# NEURON-Z1_EASYEDA.net
KiCad netlist of a schematic drawn in EasyEDA
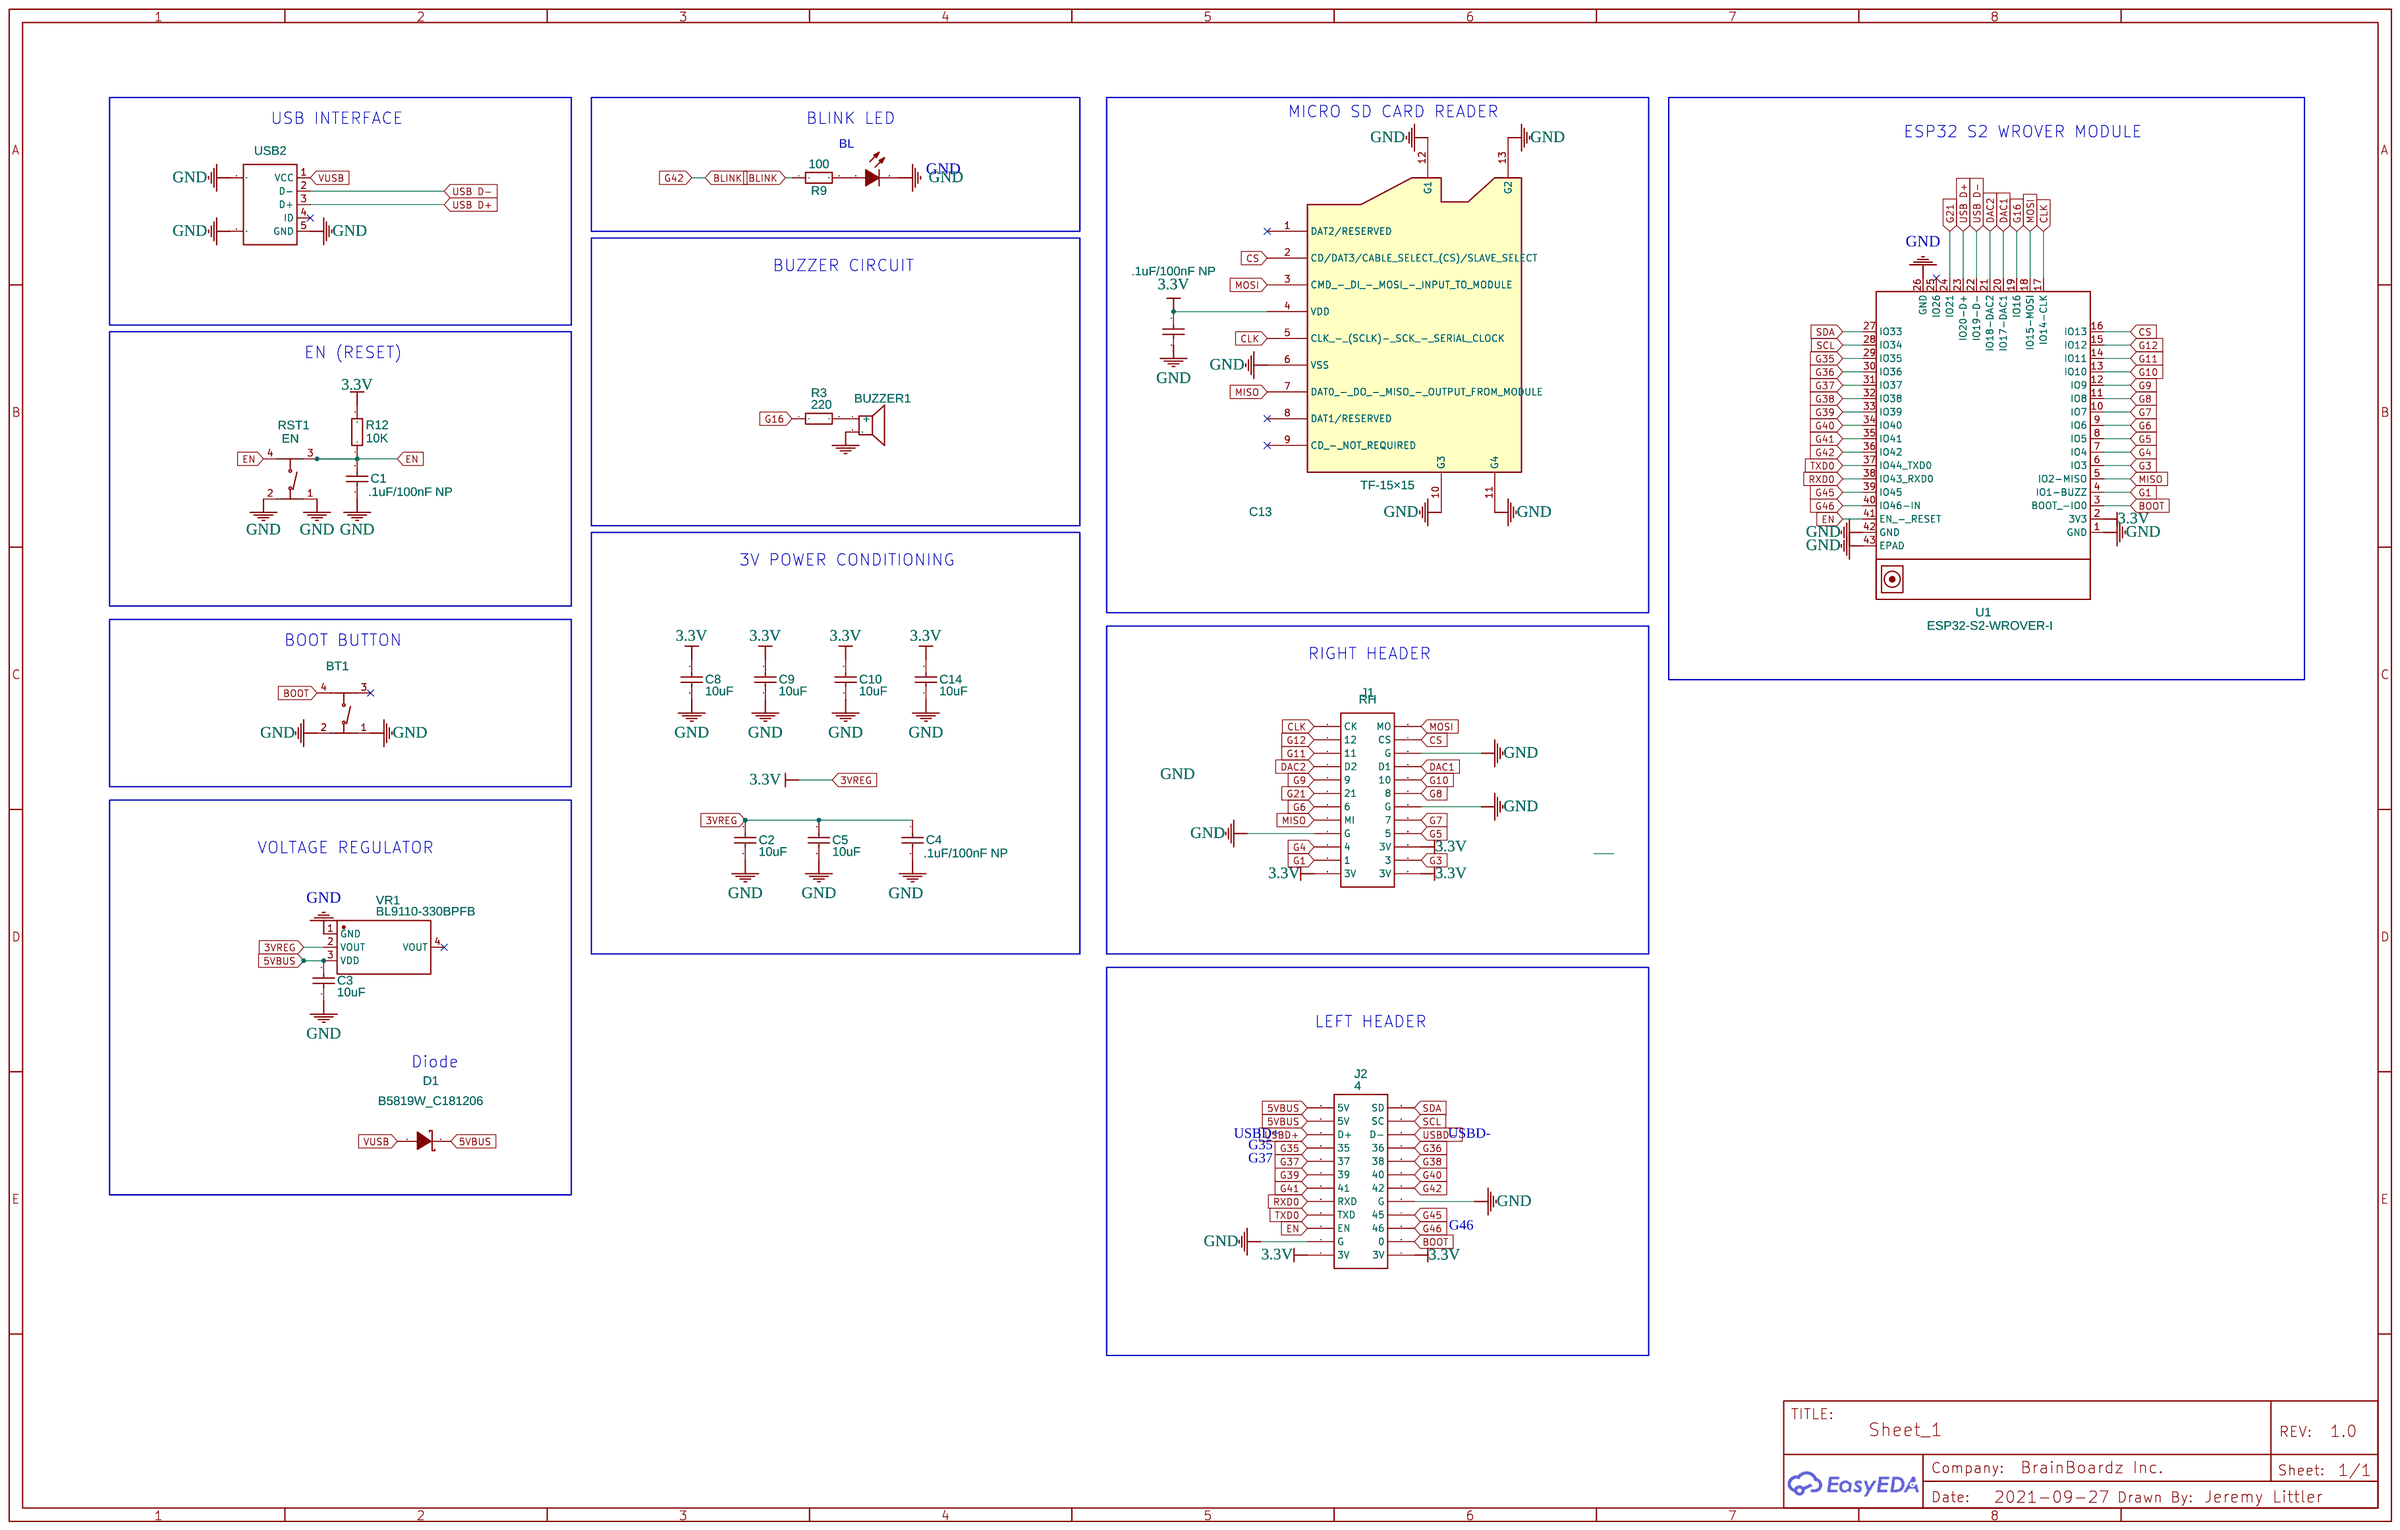
[diagram p0: schematic sheet]

(export (version "E")
  (design (tool "Eeschema 10.0.6"))
  (components
    (comp (ref "BLINK1")
      (value "15-21SYGC/S530-E2/TR8")
      (fields (field (name "BOM_Supplier Part") "C73550"))
      (libsource (lib "") (part "15-21SYGC/S530-E2/TR8"))
    )
    (comp (ref "BT1")
      (value "BOOT")
      (fields
        (field (name "BOM_Manufacturer Part") "TS-1187A-C-E-B")
        (field (name "BOM_Supplier Part") "C318887")
      )
      (libsource (lib "") (part "TS-1187A-C-E-B"))
    )
    (comp (ref "BUZZER1")
      (value "PS1240P02CT3")
      (fields (field (name "BOM_Supplier Part") "C76873"))
      (libsource (lib "") (part "PS1240P02CT3"))
    )
    (comp (ref "C1")
      (value ".1uF/100nF NP")
      (fields
        (field (name "BOM_Manufacturer Part") "CL31B104KBCNNNC")
        (field (name "BOM_Supplier Part") "C24497")
      )
      (libsource (lib "") (part "CL31B104KBCNNNC"))
    )
    (comp (ref "C2")
      (value "10uF")
      (fields
        (field (name "BOM_Manufacturer Part") "CL31A106KBHNNNE")
        (field (name "BOM_Supplier Part") "C13585")
      )
      (libsource (lib "") (part "CL31A106KBHNNNE"))
    )
    (comp (ref "C3")
      (value "10uF")
      (fields
        (field (name "BOM_Manufacturer Part") "CL31A106KBHNNNE")
        (field (name "BOM_Supplier Part") "C13585")
      )
      (libsource (lib "") (part "CL31A106KBHNNNE"))
    )
    (comp (ref "C4")
      (value ".1uF/100nF NP")
      (fields
        (field (name "BOM_Manufacturer Part") "CL31B104KBCNNNC")
        (field (name "BOM_Supplier Part") "C24497")
      )
      (libsource (lib "") (part "CL31B104KBCNNNC"))
    )
    (comp (ref "C5")
      (value "10uF")
      (fields
        (field (name "BOM_Manufacturer Part") "CL31A106KBHNNNE")
        (field (name "BOM_Supplier Part") "C13585")
      )
      (libsource (lib "") (part "CL31A106KBHNNNE"))
    )
    (comp (ref "C8")
      (value "10uF")
      (fields
        (field (name "BOM_Manufacturer Part") "CL31A106KBHNNNE")
        (field (name "BOM_Supplier Part") "C13585")
      )
      (libsource (lib "") (part "CL31A106KBHNNNE"))
    )
    (comp (ref "C9")
      (value "10uF")
      (fields
        (field (name "BOM_Manufacturer Part") "CL31A106KBHNNNE")
        (field (name "BOM_Supplier Part") "C13585")
      )
      (libsource (lib "") (part "CL31A106KBHNNNE"))
    )
    (comp (ref "C10")
      (value "10uF")
      (fields
        (field (name "BOM_Manufacturer Part") "CL31A106KBHNNNE")
        (field (name "BOM_Supplier Part") "C13585")
      )
      (libsource (lib "") (part "CL31A106KBHNNNE"))
    )
    (comp (ref "C13")
      (value ".1uF/100nF NP")
      (fields
        (field (name "BOM_Manufacturer Part") "CL31B104KBCNNNC")
        (field (name "BOM_Supplier Part") "C24497")
      )
      (libsource (lib "") (part "CL31B104KBCNNNC_1"))
    )
    (comp (ref "C14")
      (value "10uF")
      (fields
        (field (name "BOM_Manufacturer Part") "CL31A106KBHNNNE")
        (field (name "BOM_Supplier Part") "C13585")
      )
      (libsource (lib "") (part "CL31A106KBHNNNE"))
    )
    (comp (ref "D1")
      (value "B5819W_C181206")
      (fields (field (name "BOM_Manufacturer Part") "B5819W") (field (name "BOM_Supplier Part") "C181206"))
      (libsource (lib "") (part "B5819W_C181206"))
    )
    (comp (ref "J1")
      (value "RH")
      (fields (field (name "BOM_Manufacturer Part") "New SchematicLib"))
      (libsource (lib "") (part "HDR 2.54mm 2x12_1"))
    )
    (comp (ref "J2")
      (value "4")
      (fields (field (name "BOM_Manufacturer Part") "New SchematicLib"))
      (libsource (lib "") (part "HDR 2.54mm 2x12"))
    )
    (comp (ref "MICROSD1")
      (value "TF-15×15")
      (fields (field (name "BOM_Supplier Part") "C111196"))
      (libsource (lib "") (part "TF-15×15"))
    )
    (comp (ref "R3")
      (value "220")
      (fields
        (field (name "BOM_Manufacturer Part") "1206W4J0221T5E")
        (field (name "BOM_Supplier Part") "C25363")
      )
      (libsource (lib "") (part "1206W4J0221T5E"))
    )
    (comp (ref "R9")
      (value "100")
      (fields
        (field (name "BOM_Manufacturer Part") "1206W4F1000T5E")
        (field (name "BOM_Supplier Part") "C17901")
      )
      (libsource (lib "") (part "1206W4F1000T5E"))
    )
    (comp (ref "R12")
      (value "10K")
      (fields
        (field (name "BOM_Manufacturer Part") "AECR1206F10K0K9")
        (field (name "BOM_Supplier Part") "C328409")
      )
      (libsource (lib "") (part "AECR1206F10K0K9"))
    )
    (comp (ref "RST1")
      (value "EN")
      (fields
        (field (name "BOM_Manufacturer Part") "TS-1187A-C-E-B")
        (field (name "BOM_Supplier Part") "C318887")
      )
      (libsource (lib "") (part "TS-1187A-C-E-B_1"))
    )
    (comp (ref "U1") (value "ESP32-S2-WROVER-I") (libsource (lib "") (part "ESP32-S2-WROVER-I")))
    (comp (ref "USB2")
      (value "Mini USB-B 5P-Female-TH_C46398")
      (fields
        (field (name "BOM_Manufacturer Part") "MINI 5PFemale90Degree plate four feet copper shell LCPVinyl")
        (field (name "BOM_Supplier Part") "C46398")
      )
      (libsource (lib "") (part "Mini USB-B 5P-Female-TH_C46398"))
    )
    (comp (ref "VR1")
      (value "BL9110-330BPFB")
      (fields (field (name "BOM_Supplier Part") "C169246"))
      (libsource (lib "") (part "BL9110-330BPFB"))
    )
  )
  (nets
    (net (code "1") (name "3VREG") (class "Default")
      (node (ref "C10") (pin "2") (pinfunction "2_2") (pintype "input"))
      (node (ref "C13") (pin "2") (pinfunction "2_2") (pintype "input"))
      (node (ref "C14") (pin "2") (pinfunction "2_2") (pintype "input"))
      (node (ref "C2") (pin "2") (pinfunction "2_2") (pintype "input"))
      (node (ref "C4") (pin "1") (pinfunction "1_1") (pintype "input"))
      (node (ref "C5") (pin "2") (pinfunction "2_2") (pintype "input"))
      (node (ref "C8") (pin "2") (pinfunction "2_2") (pintype "input"))
      (node (ref "C9") (pin "2") (pinfunction "2_2") (pintype "input"))
      (node (ref "J1") (pin "20") (pinfunction "3V_20") (pintype "unspecified"))
      (node (ref "J1") (pin "23") (pinfunction "3V_23") (pintype "unspecified"))
      (node (ref "J1") (pin "24") (pinfunction "3V_24") (pintype "unspecified"))
      (node (ref "J2") (pin "1") (pinfunction "3V_1") (pintype "unspecified"))
      (node (ref "J2") (pin "2") (pinfunction "3V_2") (pintype "unspecified"))
      (node (ref "MICROSD1") (pin "4") (pinfunction "VDD_4") (pintype "input"))
      (node (ref "R12") (pin "2") (pinfunction "2_2") (pintype "unspecified"))
      (node (ref "U1") (pin "2") (pinfunction "3V3_2") (pintype "unspecified"))
      (node (ref "VR1") (pin "2") (pinfunction "VOUT_2") (pintype "unspecified"))
    )
    (net (code "2") (name "5VBUS") (class "Default")
      (node (ref "C3") (pin "2") (pinfunction "2_2") (pintype "input"))
      (node (ref "D1") (pin "1") (pinfunction "K_1") (pintype "unspecified"))
      (node (ref "J2") (pin "22") (pinfunction "5V_22") (pintype "unspecified"))
      (node (ref "J2") (pin "24") (pinfunction "5V_24") (pintype "unspecified"))
      (node (ref "VR1") (pin "3") (pinfunction "VDD_3") (pintype "unspecified"))
    )
    (net (code "3") (name "BLINK") (class "Default")
      (node (ref "J2") (pin "11") (pinfunction "42_11") (pintype "unspecified"))
      (node (ref "R9") (pin "1") (pinfunction "1_1") (pintype "input"))
      (node (ref "U1") (pin "36") (pinfunction "IO42_36") (pintype "unspecified"))
    )
    (net (code "4") (name "BOOT") (class "Default")
      (node (ref "BT1") (pin "4") (pinfunction "D_4") (pintype "unspecified"))
      (node (ref "J2") (pin "3") (pinfunction "0_3") (pintype "unspecified"))
      (node (ref "U1") (pin "3") (pinfunction "BOOT_-IO0_3") (pintype "unspecified"))
    )
    (net (code "5") (name "CLK") (class "Default")
      (node (ref "J1") (pin "1") (pinfunction "CK_1") (pintype "unspecified"))
      (node (ref "MICROSD1") (pin "5") (pinfunction "CLK_-_(SCLK)-_SCK_-_SERIAL_CLOCK_5") (pintype "input"))
      (node (ref "U1") (pin "17") (pinfunction "IO14-CLK_17") (pintype "unspecified"))
    )
    (net (code "6") (name "CS") (class "Default")
      (node (ref "J1") (pin "4") (pinfunction "CS_4") (pintype "unspecified"))
      (node (ref "MICROSD1") (pin "2") (pinfunction "CD/DAT3/CABLE_SELECT_(CS)/SLAVE_SELECT_2") (pintype "input"))
      (node (ref "U1") (pin "16") (pinfunction "IO13_16") (pintype "unspecified"))
    )
    (net (code "7") (name "DAC1") (class "Default")
      (node (ref "J1") (pin "8") (pinfunction "D1_8") (pintype "unspecified"))
      (node (ref "U1") (pin "20") (pinfunction "IO17-DAC1_20") (pintype "unspecified"))
    )
    (net (code "8") (name "DAC2") (class "Default")
      (node (ref "J1") (pin "7") (pinfunction "D2_7") (pintype "unspecified"))
      (node (ref "U1") (pin "21") (pinfunction "IO18-DAC2_21") (pintype "unspecified"))
    )
    (net (code "9") (name "EN") (class "Default")
      (node (ref "C1") (pin "1") (pinfunction "1_1") (pintype "input"))
      (node (ref "J2") (pin "6") (pinfunction "EN_6") (pintype "unspecified"))
      (node (ref "R12") (pin "1") (pinfunction "1_1") (pintype "unspecified"))
      (node (ref "RST1") (pin "3") (pinfunction "C_3") (pintype "unspecified"))
      (node (ref "RST1") (pin "4") (pinfunction "D_4") (pintype "unspecified"))
      (node (ref "U1") (pin "41") (pinfunction "EN_-_RESET_41") (pintype "unspecified"))
    )
    (net (code "10") (name "G1") (class "Default")
      (node (ref "J1") (pin "21") (pinfunction "1_21") (pintype "unspecified"))
      (node (ref "U1") (pin "4") (pinfunction "IO1-BUZZ_4") (pintype "unspecified"))
    )
    (net (code "11") (name "G3") (class "Default")
      (node (ref "J1") (pin "22") (pinfunction "3_22") (pintype "unspecified"))
      (node (ref "U1") (pin "6") (pinfunction "IO3_6") (pintype "unspecified"))
    )
    (net (code "12") (name "G4") (class "Default")
      (node (ref "J1") (pin "19") (pinfunction "4_19") (pintype "unspecified"))
      (node (ref "U1") (pin "7") (pinfunction "IO4_7") (pintype "unspecified"))
    )
    (net (code "13") (name "G5") (class "Default")
      (node (ref "J1") (pin "18") (pinfunction "5_18") (pintype "unspecified"))
      (node (ref "U1") (pin "8") (pinfunction "IO5_8") (pintype "unspecified"))
    )
    (net (code "14") (name "G6") (class "Default")
      (node (ref "J1") (pin "13") (pinfunction "6_13") (pintype "unspecified"))
      (node (ref "U1") (pin "9") (pinfunction "IO6_9") (pintype "unspecified"))
    )
    (net (code "15") (name "G7") (class "Default")
      (node (ref "J1") (pin "16") (pinfunction "7_16") (pintype "unspecified"))
      (node (ref "U1") (pin "10") (pinfunction "IO7_10") (pintype "unspecified"))
    )
    (net (code "16") (name "G8") (class "Default")
      (node (ref "J1") (pin "12") (pinfunction "8_12") (pintype "unspecified"))
      (node (ref "U1") (pin "11") (pinfunction "IO8_11") (pintype "unspecified"))
    )
    (net (code "17") (name "G9") (class "Default")
      (node (ref "J1") (pin "9") (pinfunction "9_9") (pintype "unspecified"))
      (node (ref "U1") (pin "12") (pinfunction "IO9_12") (pintype "unspecified"))
    )
    (net (code "18") (name "G10") (class "Default")
      (node (ref "J1") (pin "10") (pinfunction "10_10") (pintype "unspecified"))
      (node (ref "U1") (pin "13") (pinfunction "IO10_13") (pintype "unspecified"))
    )
    (net (code "19") (name "G11") (class "Default")
      (node (ref "J1") (pin "5") (pinfunction "11_5") (pintype "unspecified"))
      (node (ref "U1") (pin "14") (pinfunction "IO11_14") (pintype "unspecified"))
    )
    (net (code "20") (name "G12") (class "Default")
      (node (ref "J1") (pin "3") (pinfunction "12_3") (pintype "unspecified"))
      (node (ref "U1") (pin "15") (pinfunction "IO12_15") (pintype "unspecified"))
    )
    (net (code "21") (name "G16") (class "Default")
      (node (ref "R3") (pin "1") (pinfunction "1_1") (pintype "input"))
      (node (ref "U1") (pin "19") (pinfunction "IO16_19") (pintype "unspecified"))
    )
    (net (code "22") (name "G21") (class "Default")
      (node (ref "J1") (pin "11") (pinfunction "21_11") (pintype "unspecified"))
      (node (ref "U1") (pin "24") (pinfunction "IO21_24") (pintype "unspecified"))
    )
    (net (code "23") (name "G35") (class "Default")
      (node (ref "J2") (pin "18") (pinfunction "35_18") (pintype "unspecified"))
      (node (ref "U1") (pin "29") (pinfunction "IO35_29") (pintype "unspecified"))
    )
    (net (code "24") (name "G36") (class "Default")
      (node (ref "J2") (pin "17") (pinfunction "36_17") (pintype "unspecified"))
      (node (ref "U1") (pin "30") (pinfunction "IO36_30") (pintype "unspecified"))
    )
    (net (code "25") (name "G37") (class "Default")
      (node (ref "J2") (pin "16") (pinfunction "37_16") (pintype "unspecified"))
      (node (ref "U1") (pin "31") (pinfunction "IO37_31") (pintype "unspecified"))
    )
    (net (code "26") (name "G38") (class "Default")
      (node (ref "J2") (pin "15") (pinfunction "38_15") (pintype "unspecified"))
      (node (ref "U1") (pin "32") (pinfunction "IO38_32") (pintype "unspecified"))
    )
    (net (code "27") (name "G39") (class "Default")
      (node (ref "J2") (pin "14") (pinfunction "39_14") (pintype "unspecified"))
      (node (ref "U1") (pin "33") (pinfunction "IO39_33") (pintype "unspecified"))
    )
    (net (code "28") (name "G40") (class "Default")
      (node (ref "J2") (pin "13") (pinfunction "40_13") (pintype "unspecified"))
      (node (ref "U1") (pin "34") (pinfunction "IO40_34") (pintype "unspecified"))
    )
    (net (code "29") (name "G41") (class "Default")
      (node (ref "J2") (pin "12") (pinfunction "41_12") (pintype "unspecified"))
      (node (ref "U1") (pin "35") (pinfunction "IO41_35") (pintype "unspecified"))
    )
    (net (code "30") (name "G45") (class "Default")
      (node (ref "J2") (pin "7") (pinfunction "45_7") (pintype "unspecified"))
      (node (ref "U1") (pin "39") (pinfunction "IO45_39") (pintype "unspecified"))
    )
    (net (code "31") (name "G46") (class "Default")
      (node (ref "J2") (pin "5") (pinfunction "46_5") (pintype "unspecified"))
      (node (ref "U1") (pin "40") (pinfunction "IO46-IN_40") (pintype "unspecified"))
    )
    (net (code "32") (name "GND") (class "Default")
      (node (ref "BLINK1") (pin "2") (pinfunction "C_2") (pintype "input"))
      (node (ref "BT1") (pin "1") (pinfunction "A_1") (pintype "unspecified"))
      (node (ref "BT1") (pin "2") (pinfunction "B_2") (pintype "unspecified"))
      (node (ref "BUZZER1") (pin "2") (pinfunction "2_2") (pintype "unspecified"))
      (node (ref "C1") (pin "2") (pinfunction "2_2") (pintype "input"))
      (node (ref "C10") (pin "1") (pinfunction "1_1") (pintype "input"))
      (node (ref "C13") (pin "1") (pinfunction "1_1") (pintype "input"))
      (node (ref "C14") (pin "1") (pinfunction "1_1") (pintype "input"))
      (node (ref "C2") (pin "1") (pinfunction "1_1") (pintype "input"))
      (node (ref "C3") (pin "1") (pinfunction "1_1") (pintype "input"))
      (node (ref "C4") (pin "2") (pinfunction "2_2") (pintype "input"))
      (node (ref "C5") (pin "1") (pinfunction "1_1") (pintype "input"))
      (node (ref "C8") (pin "1") (pinfunction "1_1") (pintype "input"))
      (node (ref "C9") (pin "1") (pinfunction "1_1") (pintype "input"))
      (node (ref "J1") (pin "14") (pinfunction "G_14") (pintype "unspecified"))
      (node (ref "J1") (pin "17") (pinfunction "G_17") (pintype "unspecified"))
      (node (ref "J1") (pin "6") (pinfunction "G_6") (pintype "unspecified"))
      (node (ref "J2") (pin "4") (pinfunction "G_4") (pintype "unspecified"))
      (node (ref "J2") (pin "9") (pinfunction "G_9") (pintype "unspecified"))
      (node (ref "MICROSD1") (pin "10") (pinfunction "G3_10") (pintype "input"))
      (node (ref "MICROSD1") (pin "11") (pinfunction "G4_11") (pintype "input"))
      (node (ref "MICROSD1") (pin "12") (pinfunction "G1_12") (pintype "input"))
      (node (ref "MICROSD1") (pin "13") (pinfunction "G2_13") (pintype "input"))
      (node (ref "MICROSD1") (pin "6") (pinfunction "VSS_6") (pintype "input"))
      (node (ref "RST1") (pin "1") (pinfunction "A_1") (pintype "unspecified"))
      (node (ref "RST1") (pin "2") (pinfunction "B_2") (pintype "unspecified"))
      (node (ref "U1") (pin "1") (pinfunction "GND_1") (pintype "unspecified"))
      (node (ref "U1") (pin "26") (pinfunction "GND_26") (pintype "unspecified"))
      (node (ref "U1") (pin "42") (pinfunction "GND_42") (pintype "unspecified"))
      (node (ref "U1") (pin "43") (pinfunction "EPAD_43") (pintype "unspecified"))
      (node (ref "USB2") (pin "0") (pinfunction "0_0") (pintype "unspecified"))
      (node (ref "USB2") (pin "5") (pinfunction "GND_5") (pintype "input"))
      (node (ref "VR1") (pin "1") (pinfunction "GND_1") (pintype "unspecified"))
    )
    (net (code "33") (name "MISO") (class "Default")
      (node (ref "J1") (pin "15") (pinfunction "MI_15") (pintype "unspecified"))
      (node (ref "MICROSD1") (pin "7") (pinfunction "DAT0_-_DO_-_MISO_-_OUTPUT_FROM_MODULE_7") (pintype "input"))
      (node (ref "U1") (pin "5") (pinfunction "IO2-MISO_5") (pintype "unspecified"))
    )
    (net (code "34") (name "MOSI") (class "Default")
      (node (ref "J1") (pin "2") (pinfunction "MO_2") (pintype "unspecified"))
      (node (ref "MICROSD1") (pin "3") (pinfunction "CMD_-_DI_-_MOSI_-_INPUT_TO_MODULE_3") (pintype "input"))
      (node (ref "U1") (pin "18") (pinfunction "IO15-MOSI_18") (pintype "unspecified"))
    )
    (net (code "35") (name "Net-(BLINK1-A)") (class "Default")
      (node (ref "BLINK1") (pin "1") (pinfunction "A_1") (pintype "input"))
      (node (ref "R9") (pin "2") (pinfunction "2_2") (pintype "input"))
    )
    (net (code "36") (name "Net-(BUZZER1-+)") (class "Default")
      (node (ref "BUZZER1") (pin "1") (pinfunction "+_1") (pintype "unspecified"))
      (node (ref "R3") (pin "2") (pinfunction "2_2") (pintype "input"))
    )
    (net (code "37") (name "RXD0") (class "Default")
      (node (ref "J2") (pin "10") (pinfunction "RXD_10") (pintype "unspecified"))
      (node (ref "U1") (pin "38") (pinfunction "IO43_RXD0_38") (pintype "unspecified"))
    )
    (net (code "38") (name "SCL") (class "Default")
      (node (ref "J2") (pin "21") (pinfunction "SC_21") (pintype "unspecified"))
      (node (ref "U1") (pin "28") (pinfunction "IO34_28") (pintype "unspecified"))
    )
    (net (code "39") (name "SDA") (class "Default")
      (node (ref "J2") (pin "23") (pinfunction "SD_23") (pintype "unspecified"))
      (node (ref "U1") (pin "27") (pinfunction "IO33_27") (pintype "unspecified"))
    )
    (net (code "40") (name "TXD0") (class "Default")
      (node (ref "J2") (pin "8") (pinfunction "TXD_8") (pintype "unspecified"))
      (node (ref "U1") (pin "37") (pinfunction "IO44_TXD0_37") (pintype "unspecified"))
    )
    (net (code "41") (name "USB D+") (class "Default")
      (node (ref "U1") (pin "23") (pinfunction "IO20-D+_23") (pintype "unspecified"))
      (node (ref "USB2") (pin "3") (pinfunction "D+_3") (pintype "input"))
    )
    (net (code "42") (name "USB D-") (class "Default")
      (node (ref "U1") (pin "22") (pinfunction "IO19-D-_22") (pintype "unspecified"))
      (node (ref "USB2") (pin "2") (pinfunction "D-_2") (pintype "input"))
    )
    (net (code "43") (name "USBD+") (class "Default")
      (node (ref "J2") (pin "20") (pinfunction "D+_20") (pintype "unspecified"))
    )
    (net (code "44") (name "USBD-") (class "Default")
      (node (ref "J2") (pin "19") (pinfunction "D-_19") (pintype "unspecified"))
    )
    (net (code "45") (name "VUSB") (class "Default")
      (node (ref "D1") (pin "2") (pinfunction "A_2") (pintype "unspecified"))
      (node (ref "USB2") (pin "1") (pinfunction "VCC_1") (pintype "input"))
    )
    (net (code "46") (name "unconnected-(BT1-C-Pad3)") (class "Default")
      (node (ref "BT1") (pin "3") (pinfunction "C_3") (pintype "unspecified+no_connect"))
    )
    (net (code "47") (name "unconnected-(MICROSD1-CD_-_NOT_REQUIRED-Pad9)") (class "Default")
      (node (ref "MICROSD1") (pin "9") (pinfunction "CD_-_NOT_REQUIRED_9") (pintype "input+no_connect"))
    )
    (net (code "48") (name "unconnected-(MICROSD1-DAT1{slash}RESERVED-Pad8)") (class "Default")
      (node (ref "MICROSD1") (pin "8") (pinfunction "DAT1/RESERVED_8") (pintype "input+no_connect"))
    )
    (net (code "49") (name "unconnected-(MICROSD1-DAT2{slash}RESERVED-Pad1)") (class "Default")
      (node (ref "MICROSD1") (pin "1") (pinfunction "DAT2/RESERVED_1") (pintype "input+no_connect"))
    )
    (net (code "50") (name "unconnected-(U1-IO26-Pad25)") (class "Default")
      (node (ref "U1") (pin "25") (pinfunction "IO26_25") (pintype "unspecified+no_connect"))
    )
    (net (code "51") (name "unconnected-(USB2-ID-Pad4)") (class "Default")
      (node (ref "USB2") (pin "4") (pinfunction "ID_4") (pintype "input+no_connect"))
    )
    (net (code "52") (name "unconnected-(VR1-VOUT-Pad4)") (class "Default")
      (node (ref "VR1") (pin "4") (pinfunction "VOUT_4") (pintype "unspecified+no_connect"))
    )
  )
)
